# power_PCB_layout.net
KiCad netlist of a schematic drawn in EAGLE
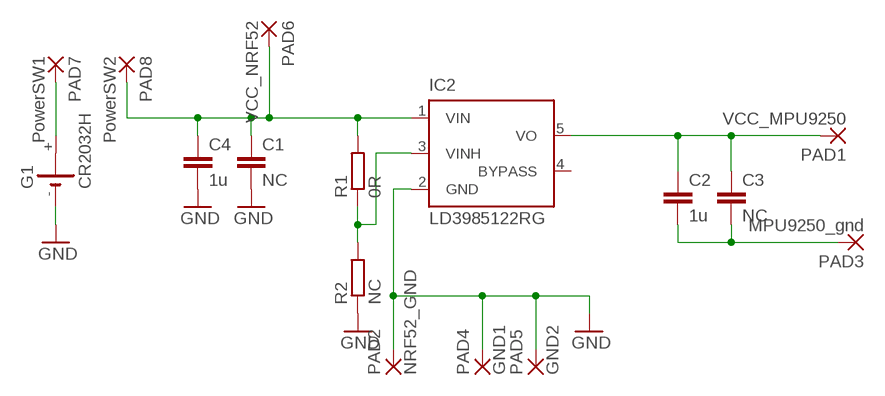
[diagram p0: schematic, sheet 1]

(export (version "E")
  (design (tool "Eeschema 10.0.6"))
  (components
    (comp (ref "C1")
      (value "NC")
      (footprint "eagle-import:C0805")
      (libsource (lib "eagle-import") (part "C-EUC0805"))
    )
    (comp (ref "C2")
      (value "1u")
      (footprint "eagle-import:C0805")
      (libsource (lib "eagle-import") (part "C-EUC0805"))
    )
    (comp (ref "C3")
      (value "NC")
      (footprint "eagle-import:C0805")
      (libsource (lib "eagle-import") (part "C-EUC0805"))
    )
    (comp (ref "C4")
      (value "1u")
      (footprint "eagle-import:C0805")
      (libsource (lib "eagle-import") (part "C-EUC0805"))
    )
    (comp (ref "G1")
      (value "CR2032H")
      (footprint "eagle-import:CR2032H")
      (libsource (lib "eagle-import") (part "CR2032H"))
    )
    (comp (ref "IC2")
      (value "LD3985122RG")
      (footprint "eagle-import:TSOT23-5L")
      (libsource (lib "eagle-import") (part "LD3985G122R"))
    )
    (comp (ref "PAD1")
      (value "VCC_MPU9250")
      (footprint "eagle-import:2,54_1,0")
      (libsource (lib "eagle-import") (part "2,54/1,0"))
    )
    (comp (ref "PAD2")
      (value "NRF52_GND")
      (footprint "eagle-import:2,54_1,0")
      (libsource (lib "eagle-import") (part "2,54/1,0"))
    )
    (comp (ref "PAD3")
      (value "MPU9250_gnd")
      (footprint "eagle-import:2,54_1,0")
      (libsource (lib "eagle-import") (part "2,54/1,0"))
    )
    (comp (ref "PAD4")
      (value "GND1")
      (footprint "eagle-import:2,54_1,0")
      (libsource (lib "eagle-import") (part "2,54/1,0"))
    )
    (comp (ref "PAD5")
      (value "GND2")
      (footprint "eagle-import:2,54_1,0")
      (libsource (lib "eagle-import") (part "2,54/1,0"))
    )
    (comp (ref "PAD6")
      (value "VCC_NRF52")
      (footprint "eagle-import:2,54_1,0")
      (libsource (lib "eagle-import") (part "2,54/1,0"))
    )
    (comp (ref "PAD7")
      (value "PowerSW1")
      (footprint "eagle-import:2,54_1,0")
      (libsource (lib "eagle-import") (part "2,54/1,0"))
    )
    (comp (ref "PAD8")
      (value "PowerSW2")
      (footprint "eagle-import:2,54_1,0")
      (libsource (lib "eagle-import") (part "2,54/1,0"))
    )
    (comp (ref "R1")
      (value "0R")
      (footprint "eagle-import:R1206")
      (libsource (lib "eagle-import") (part "R-EU_R1206"))
    )
    (comp (ref "R2")
      (value "NC")
      (footprint "eagle-import:R0603")
      (libsource (lib "eagle-import") (part "R-EU_R0603"))
    )
  )
  (nets
    (net (code "1") (name "GND") (class "Default")
      (node (ref "C1") (pin "2") (pinfunction "2_2") (pintype "passive"))
      (node (ref "C4") (pin "2") (pinfunction "2_2") (pintype "passive"))
      (node (ref "G1") (pin "-") (pinfunction "-_-") (pintype "passive"))
      (node (ref "IC2") (pin "2") (pinfunction "GND_2") (pintype "power_in"))
      (node (ref "PAD2") (pin "1") (pinfunction "P_1") (pintype "passive"))
      (node (ref "PAD4") (pin "1") (pinfunction "P_1") (pintype "passive"))
      (node (ref "PAD5") (pin "1") (pinfunction "P_1") (pintype "passive"))
      (node (ref "R2") (pin "1") (pinfunction "1_1") (pintype "passive"))
    )
    (net (code "2") (name "Net-(IC2-VIN)") (class "Default")
      (node (ref "C1") (pin "1") (pinfunction "1_1") (pintype "passive"))
      (node (ref "C4") (pin "1") (pinfunction "1_1") (pintype "passive"))
      (node (ref "IC2") (pin "1") (pinfunction "VIN_1") (pintype "input"))
      (node (ref "PAD6") (pin "1") (pinfunction "P_1") (pintype "passive"))
      (node (ref "PAD8") (pin "1") (pinfunction "P_1") (pintype "passive"))
      (node (ref "R1") (pin "2") (pinfunction "2_2") (pintype "passive"))
    )
    (net (code "3") (name "Net-(IC2-VINH)") (class "Default")
      (node (ref "IC2") (pin "3") (pinfunction "VINH_3") (pintype "input"))
      (node (ref "R1") (pin "1") (pinfunction "1_1") (pintype "passive"))
      (node (ref "R2") (pin "2") (pinfunction "2_2") (pintype "passive"))
    )
    (net (code "4") (name "Net-(IC2-VO)") (class "Default")
      (node (ref "C2") (pin "1") (pinfunction "1_1") (pintype "passive"))
      (node (ref "C3") (pin "1") (pinfunction "1_1") (pintype "passive"))
      (node (ref "IC2") (pin "5") (pinfunction "VO_5") (pintype "output"))
      (node (ref "PAD1") (pin "1") (pinfunction "P_1") (pintype "passive"))
    )
    (net (code "5") (name "Net-(PAD3-P)") (class "Default")
      (node (ref "C2") (pin "2") (pinfunction "2_2") (pintype "passive"))
      (node (ref "C3") (pin "2") (pinfunction "2_2") (pintype "passive"))
      (node (ref "PAD3") (pin "1") (pinfunction "P_1") (pintype "passive"))
    )
    (net (code "6") (name "Net-(PAD7-P)") (class "Default")
      (node (ref "G1") (pin "+") (pinfunction "+_+") (pintype "passive"))
      (node (ref "PAD7") (pin "1") (pinfunction "P_1") (pintype "passive"))
    )
    (net (code "7") (name "unconnected-(G1-+-Pad+@1)") (class "Default")
      (node (ref "G1") (pin "+@1") (pinfunction "+_+@1") (pintype "passive"))
    )
    (net (code "8") (name "unconnected-(IC2-BYPASS-Pad4)") (class "Default")
      (node (ref "IC2") (pin "4") (pinfunction "BYPASS_4") (pintype "passive"))
    )
  )
)
